# CH32F207_V307V-R3-2v0.net
KiCad netlist of a schematic drawn in Altium Designer
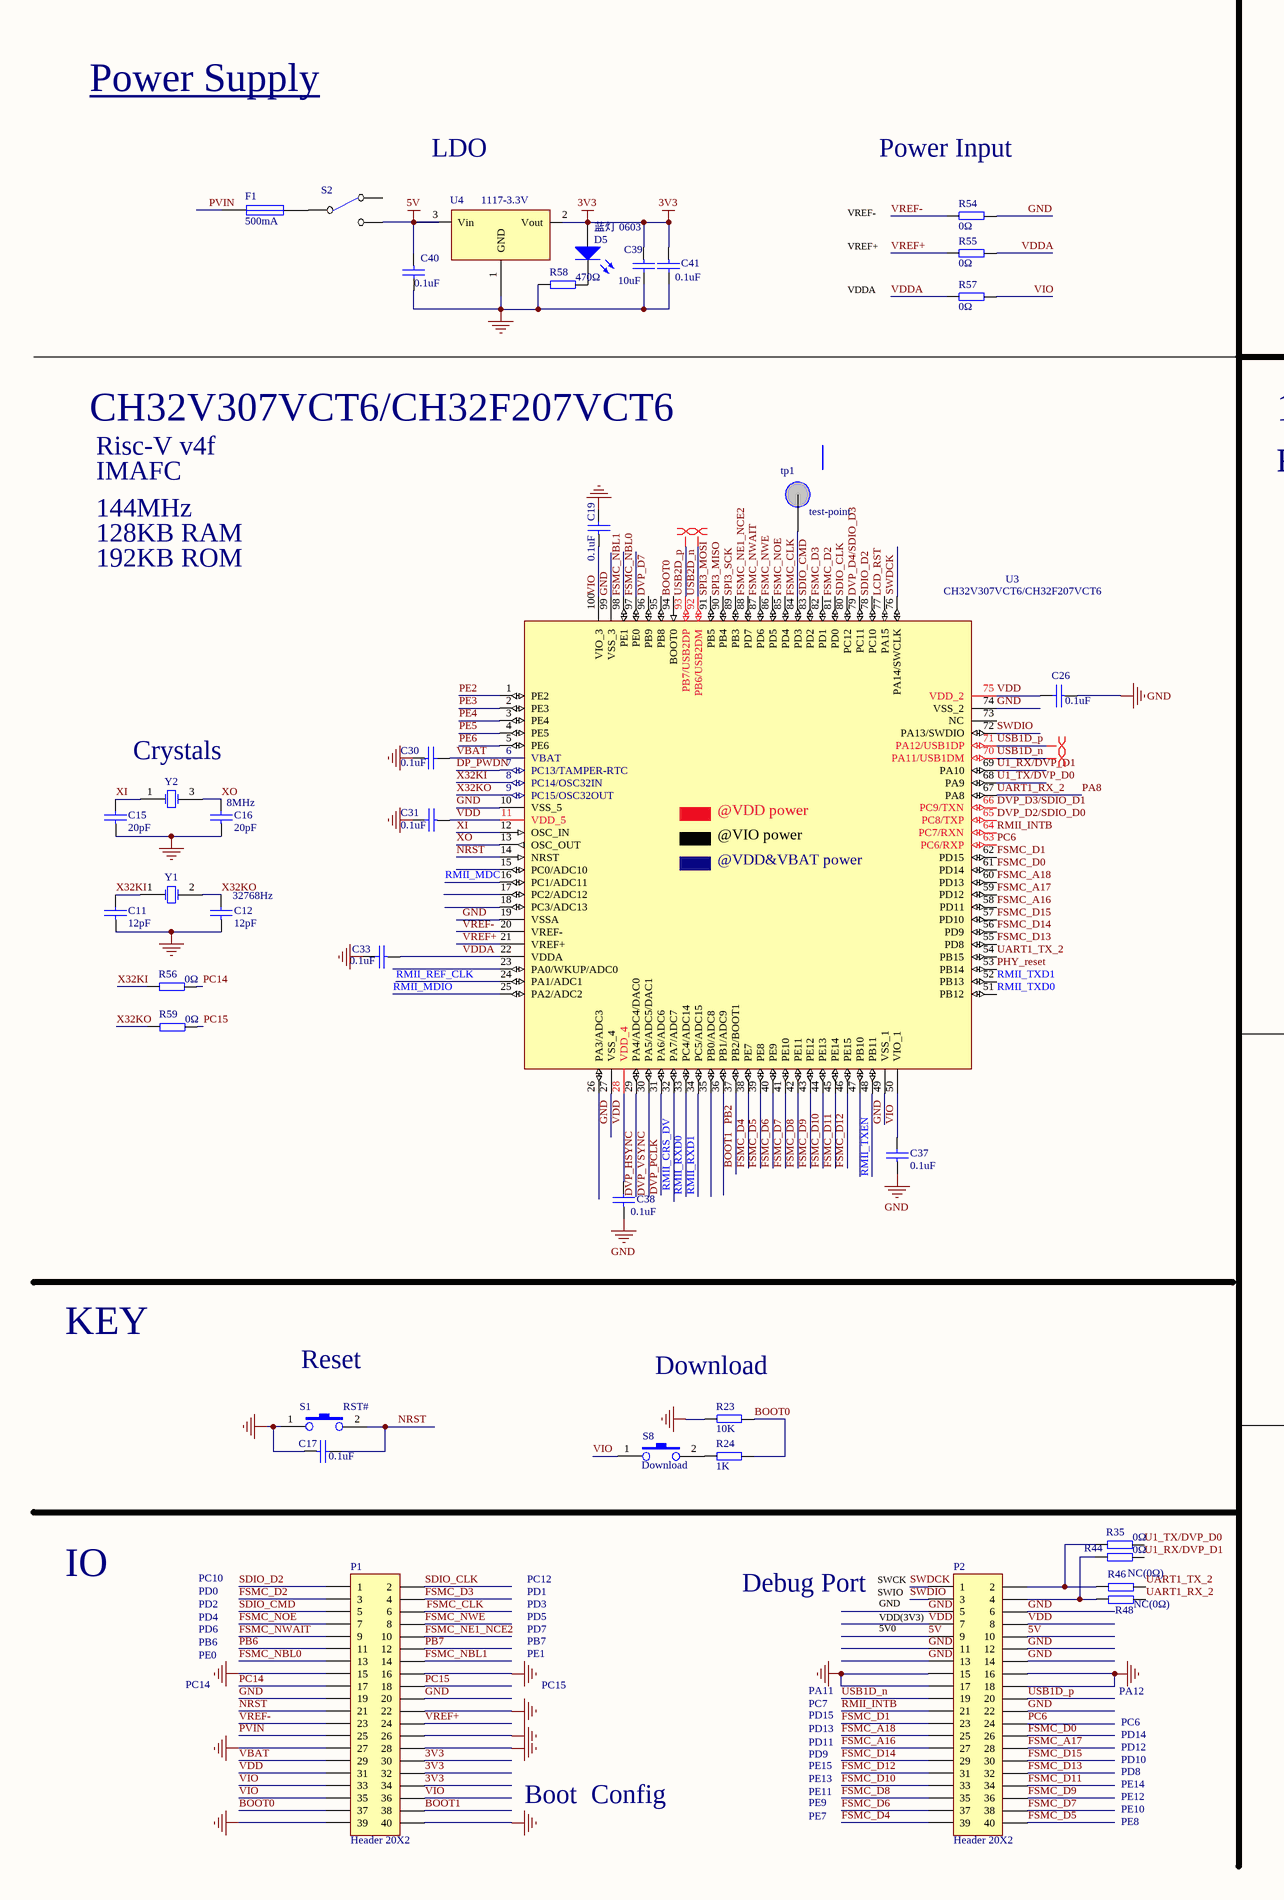
[diagram p0: CH32F207&V307V-R3-2v0.SchDoc, left]
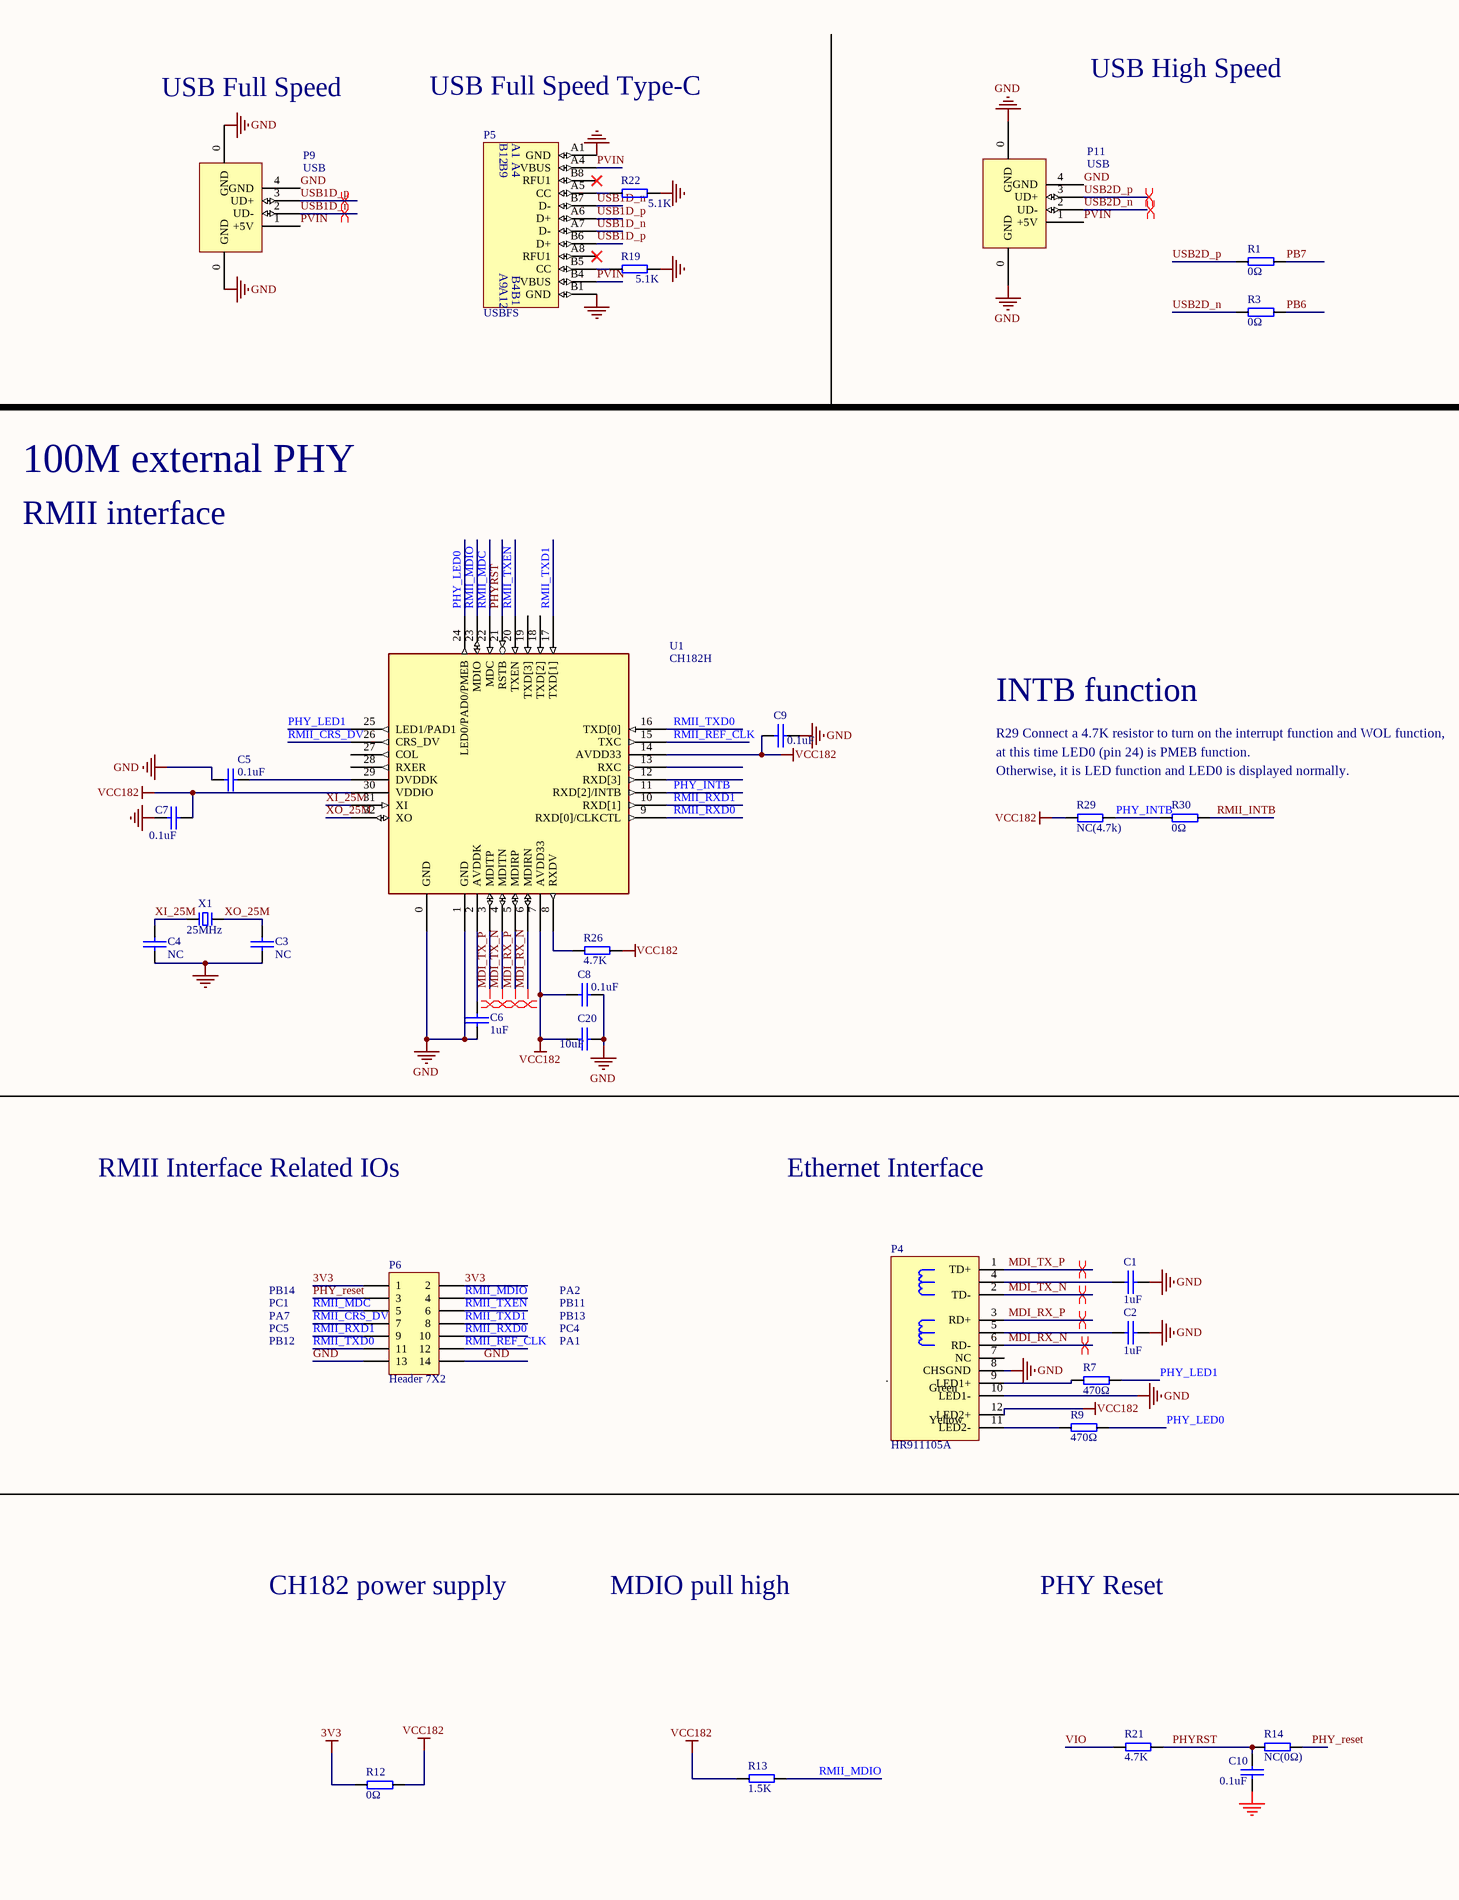
[diagram p1: CH32F207&V307V-R3-2v0.SchDoc, right]

(export (version "E")
  (design (tool "Eeschema 10.0.6"))
  (components
    (comp (ref "C1")
      (value "1uF")
      (footprint "0603_C")
      (description "Capacitor")
      (libsource (lib "wch_sch_others") (part "CAP"))
    )
    (comp (ref "C2")
      (value "1uF")
      (footprint "0603_C")
      (description "Capacitor")
      (libsource (lib "wch_sch_others") (part "CAP"))
    )
    (comp (ref "C3")
      (value "NC")
      (footprint "0603_C")
      (description "Capacitor")
      (libsource (lib "wch_sch_others") (part "CAP"))
    )
    (comp (ref "C4")
      (value "NC")
      (footprint "0603_C")
      (description "Capacitor")
      (libsource (lib "wch_sch_others") (part "CAP"))
    )
    (comp (ref "C5")
      (value "0.1uF")
      (footprint "0603_C")
      (description "Capacitor")
      (libsource (lib "wch_sch_others") (part "CAP"))
    )
    (comp (ref "C6")
      (value "1uF")
      (footprint "0603_C")
      (description "Capacitor")
      (libsource (lib "wch_sch_others") (part "CAP"))
    )
    (comp (ref "C7")
      (value "0.1uF")
      (footprint "0603_C")
      (description "Capacitor")
      (libsource (lib "wch_sch_others") (part "CAP"))
    )
    (comp (ref "C8")
      (value "0.1uF")
      (footprint "0603_C")
      (description "Capacitor")
      (libsource (lib "wch_sch_others") (part "CAP"))
    )
    (comp (ref "C9")
      (value "0.1uF")
      (footprint "0603_C")
      (description "Capacitor")
      (libsource (lib "wch_sch_others") (part "CAP"))
    )
    (comp (ref "C10")
      (value "0.1uF")
      (footprint "0603_C")
      (description "Capacitor")
      (libsource (lib "*") (part "CAP"))
    )
    (comp (ref "C11")
      (value "12pF")
      (footprint "0603_C")
      (description "Capacitor")
      (libsource (lib "*") (part "CAP"))
    )
    (comp (ref "C12")
      (value "12pF")
      (footprint "0603_C")
      (description "Capacitor")
      (libsource (lib "*") (part "CAP"))
    )
    (comp (ref "C15")
      (value "20pF")
      (footprint "0603_C")
      (description "Capacitor")
      (libsource (lib "*") (part "CAP"))
    )
    (comp (ref "C16")
      (value "20pF")
      (footprint "0603_C")
      (description "Capacitor")
      (libsource (lib "*") (part "CAP"))
    )
    (comp (ref "C17")
      (value "0.1uF")
      (footprint "0603_C")
      (description "Capacitor")
      (libsource (lib "") (part "CAP_1"))
    )
    (comp (ref "C19")
      (value "0.1uF")
      (footprint "0603_C")
      (description "Capacitor")
      (libsource (lib "*") (part "CAP"))
    )
    (comp (ref "C20")
      (value "10uF")
      (footprint "0603_C")
      (description "Capacitor")
      (libsource (lib "wch_sch_others") (part "CAP"))
    )
    (comp (ref "C26")
      (value "0.1uF")
      (footprint "0603_C")
      (description "Capacitor")
      (libsource (lib "*") (part "CAP"))
    )
    (comp (ref "C30")
      (value "0.1uF")
      (footprint "0603_C")
      (description "Capacitor")
      (libsource (lib "*") (part "CAP"))
    )
    (comp (ref "C31")
      (value "0.1uF")
      (footprint "0603_C")
      (description "Capacitor")
      (libsource (lib "*") (part "CAP"))
    )
    (comp (ref "C33")
      (value "0.1uF")
      (footprint "0603_C")
      (description "Capacitor")
      (libsource (lib "*") (part "CAP"))
    )
    (comp (ref "C37")
      (value "0.1uF")
      (footprint "0603_C")
      (description "Capacitor")
      (libsource (lib "*") (part "CAP"))
    )
    (comp (ref "C38")
      (value "0.1uF")
      (footprint "0603_C")
      (description "Capacitor")
      (libsource (lib "*") (part "CAP"))
    )
    (comp (ref "C39")
      (value "10uF")
      (footprint "0603_C")
      (description "Capacitor")
      (libsource (lib "*") (part "CAP"))
    )
    (comp (ref "C40")
      (value "0.1uF")
      (footprint "0603_C")
      (description "Capacitor")
      (libsource (lib "*") (part "CAP"))
    )
    (comp (ref "C41")
      (value "0.1uF")
      (footprint "0603_C")
      (description "Capacitor")
      (libsource (lib "*") (part "CAP"))
    )
    (comp (ref "D5")
      (value "蓝灯 0603")
      (footprint "0603_LED_S1")
      (description "发光二极管")
      (libsource (lib "Miscellaneous Devices LC") (part "0603 蓝灯"))
    )
    (comp (ref "F1")
      (value "500mA")
      (footprint "0805")
      (description "Fuse")
      (fields (field (name "PUBLISHER") "Altium Limited"))
      (libsource (lib "Miscellaneous Devices") (part "Fuse 1"))
    )
    (comp (ref "P1")
      (value "Header 20X2")
      (footprint "HDR2X20")
      (description "Header, 20-Pin, Dual row")
      (fields (field (name "PUBLISHER") "Altium Limited"))
      (libsource (lib "Miscellaneous Connectors") (part "Header 20X2"))
    )
    (comp (ref "P2")
      (value "Header 20X2")
      (footprint "HDR2X20")
      (description "Header, 20-Pin, Dual row")
      (fields (field (name "PUBLISHER") "Altium Limited"))
      (libsource (lib "Miscellaneous Connectors") (part "Header 20X2"))
    )
    (comp (ref "P4")
      (value "HR911105A")
      (footprint "HR911105A")
      (libsource (lib "wch_sch_others") (part "HR911105A_1"))
    )
    (comp (ref "P5")
      (value "USBFS")
      (footprint "TYPE-C-Receptacle-2.0")
      (libsource (lib "*") (part "TYPE-C1"))
    )
    (comp (ref "P6")
      (value "Header 7X2")
      (footprint "IDC14-2.54mm")
      (description "Header, 7-Pin, Dual row")
      (fields (field (name "PUBLISHER") "Altium Limited"))
      (libsource (lib "Miscellaneous Connectors") (part "Header 7X2"))
    )
    (comp (ref "P9")
      (value "USB")
      (footprint "USBAF")
      (description "USB Port")
      (libsource (lib "CHXXX") (part "USB"))
    )
    (comp (ref "P11")
      (value "USB")
      (footprint "USBAF")
      (description "USB Port")
      (libsource (lib "CHXXX") (part "USB"))
    )
    (comp (ref "R1") (value "0Ω") (footprint "0603") (libsource (lib "wch_sch_others") (part "RES")))
    (comp (ref "R3") (value "0Ω") (footprint "0603") (libsource (lib "wch_sch_others") (part "RES")))
    (comp (ref "R7") (value "470Ω") (footprint "0603") (libsource (lib "wch_sch_others") (part "RES")))
    (comp (ref "R9") (value "470Ω") (footprint "0603") (libsource (lib "wch_sch_others") (part "RES")))
    (comp (ref "R12") (value "0Ω") (footprint "0603") (libsource (lib "wch_sch_others") (part "RES")))
    (comp (ref "R13") (value "1.5K") (footprint "0603") (libsource (lib "wch_sch_others") (part "RES")))
    (comp (ref "R14") (value "NC(0Ω)") (footprint "0603") (libsource (lib "wch_sch_others") (part "RES")))
    (comp (ref "R19") (value "5.1K") (footprint "0603") (libsource (lib "wch_sch_others") (part "RES")))
    (comp (ref "R21") (value "4.7K") (footprint "0603") (libsource (lib "wch_sch_others") (part "RES")))
    (comp (ref "R22") (value "5.1K") (footprint "0603") (libsource (lib "wch_sch_others") (part "RES")))
    (comp (ref "R23") (value "10K") (footprint "0603") (libsource (lib "wch_sch_others") (part "RES")))
    (comp (ref "R24") (value "1K") (footprint "0603") (libsource (lib "wch_sch_others") (part "RES")))
    (comp (ref "R26") (value "4.7K") (footprint "0603") (libsource (lib "wch_sch_others") (part "RES")))
    (comp (ref "R29") (value "NC(4.7k)") (footprint "0603") (libsource (lib "wch_sch_others") (part "RES")))
    (comp (ref "R30") (value "0Ω") (footprint "0603") (libsource (lib "wch_sch_others") (part "RES")))
    (comp (ref "R35") (value "0Ω") (footprint "0603") (libsource (lib "wch_sch_others") (part "RES")))
    (comp (ref "R44") (value "0Ω") (footprint "0603") (libsource (lib "wch_sch_others") (part "RES")))
    (comp (ref "R46") (value "NC(0Ω)") (footprint "0603") (libsource (lib "wch_sch_others") (part "RES")))
    (comp (ref "R48") (value "NC(0Ω)") (footprint "0603") (libsource (lib "wch_sch_others") (part "RES")))
    (comp (ref "R54") (value "0Ω") (footprint "0603") (libsource (lib "wch_sch_others") (part "RES")))
    (comp (ref "R55") (value "0Ω") (footprint "0603") (libsource (lib "wch_sch_others") (part "RES")))
    (comp (ref "R56") (value "0Ω") (footprint "0603") (libsource (lib "wch_sch_others") (part "RES")))
    (comp (ref "R57") (value "0Ω") (footprint "0603") (libsource (lib "wch_sch_others") (part "RES")))
    (comp (ref "R58") (value "470Ω") (footprint "0603") (libsource (lib "wch_sch_others") (part "RES")))
    (comp (ref "R59") (value "0Ω") (footprint "0603") (libsource (lib "wch_sch_others") (part "RES")))
    (comp (ref "S1")
      (value "RST#")
      (footprint "SMD_6.1x3.65x2.5mm-KEY")
      (libsource (lib "wch_sch_others") (part "KEY1"))
    )
    (comp (ref "S2")
      (value "SW SPDT")
      (footprint "Horizontal Slide Switch_8.7x4.4mm-2D")
      (libsource (lib "*") (part "SW SPDT"))
    )
    (comp (ref "S8")
      (value "Download")
      (footprint "SMD_6.1x3.65x2.5mm-KEY")
      (libsource (lib "wch_sch_others") (part "KEY1"))
    )
    (comp (ref "tp1")
      (value "test-point")
      (footprint "POINT")
      (description "测试点")
      (libsource (lib "五向开关") (part "test-point"))
    )
    (comp (ref "U1")
      (value "CH182H")
      (footprint "QFN32_5X5")
      (description "MII/RMII 10/100M Ethernet PHY (Transceiver) with auto MDIX")
      (libsource (lib "CHXXX") (part "CH182H"))
    )
    (comp (ref "U3")
      (value "CH32V307VCT6/CH32F207VCT6")
      (footprint "LQFP100")
      (description "RISC-V FPU HD-MCU, 144MHz, USB_480M, USB OTG, 1000M Ethernet MAC, 2*CAN, FSMC+DVP")
      (libsource (lib "CHXXX") (part "CH32V307V"))
    )
    (comp (ref "U4")
      (value "1117-3.3V")
      (footprint "SOT-223")
      (libsource (lib "wch_sch_others") (part "1117-3.3V"))
    )
    (comp (ref "X1")
      (value "25MHz")
      (footprint "SMD-3225_4P")
      (description "2脚无源脚晶振")
      (libsource (lib "10.1 - 保险丝-晶振") (part "XTAL-2P"))
    )
    (comp (ref "Y1")
      (value "32768Hz")
      (footprint "FC-135")
      (description "Crystal Oscillator")
      (fields (field (name "PUBLISHER") "Altium Limited"))
      (libsource (lib "*") (part "XTAL"))
    )
    (comp (ref "Y2")
      (value "8MHz")
      (footprint "SMD-3225_4P")
      (description "Crystal Oscillator")
      (fields (field (name "PUBLISHER") "Altium Limited"))
      (libsource (lib "") (part "XTAL_1"))
    )
  )
  (nets
    (net (code "2") (name "/BOOT0") (class "Default")
      (node (ref "P1") (pin "37") (pinfunction "37_37") (pintype "passive"))
      (node (ref "R23") (pin "1") (pintype "passive"))
      (node (ref "R24") (pin "1") (pintype "passive"))
      (node (ref "U3") (pin "94") (pinfunction "BOOT0_94") (pintype "input"))
    )
    (net (code "3") (name "/BOOT1") (class "Default")
      (node (ref "P1") (pin "38") (pinfunction "38_38") (pintype "passive"))
      (node (ref "U3") (pin "37") (pinfunction "PB2/BOOT1_37") (pintype "bidirectional"))
    )
    (net (code "4") (name "/DP_PWDN") (class "Default")
      (node (ref "U3") (pin "7") (pinfunction "PC13/TAMPER-RTC_7") (pintype "bidirectional"))
    )
    (net (code "5") (name "/DVP_D2{slash}SDIO_D0") (class "Default")
      (node (ref "U3") (pin "65") (pinfunction "PC8/TXP_65") (pintype "bidirectional"))
    )
    (net (code "6") (name "/DVP_D3{slash}SDIO_D1") (class "Default")
      (node (ref "U3") (pin "66") (pinfunction "PC9/TXN_66") (pintype "bidirectional"))
    )
    (net (code "7") (name "/DVP_D4{slash}SDIO_D3") (class "Default")
      (node (ref "U3") (pin "79") (pinfunction "PC11_79") (pintype "bidirectional"))
    )
    (net (code "8") (name "/DVP_D7") (class "Default")
      (node (ref "U3") (pin "96") (pinfunction "PB9_96") (pintype "bidirectional"))
    )
    (net (code "9") (name "/DVP_HSYNC") (class "Default")
      (node (ref "U3") (pin "29") (pinfunction "PA4/ADC4/DAC0_29") (pintype "bidirectional"))
    )
    (net (code "10") (name "/DVP_PCLK") (class "Default")
      (node (ref "U3") (pin "31") (pinfunction "PA6/ADC6_31") (pintype "bidirectional"))
    )
    (net (code "11") (name "/DVP_VSYNC") (class "Default")
      (node (ref "U3") (pin "30") (pinfunction "PA5/ADC5/DAC1_30") (pintype "bidirectional"))
    )
    (net (code "12") (name "/FSMC_A16") (class "Default")
      (node (ref "P2") (pin "27") (pinfunction "27_27") (pintype "passive"))
      (node (ref "U3") (pin "58") (pinfunction "PD11_58") (pintype "bidirectional"))
    )
    (net (code "13") (name "/FSMC_A17") (class "Default")
      (node (ref "P2") (pin "28") (pinfunction "28_28") (pintype "passive"))
      (node (ref "U3") (pin "59") (pinfunction "PD12_59") (pintype "bidirectional"))
    )
    (net (code "14") (name "/FSMC_A18") (class "Default")
      (node (ref "P2") (pin "25") (pinfunction "25_25") (pintype "passive"))
      (node (ref "U3") (pin "60") (pinfunction "PD13_60") (pintype "bidirectional"))
    )
    (net (code "15") (name "/FSMC_CLK") (class "Default")
      (node (ref "P1") (pin "6") (pinfunction "6_6") (pintype "passive"))
      (node (ref "U3") (pin "84") (pinfunction "PD3_84") (pintype "bidirectional"))
      (node (ref "tp1") (pin "1") (pinfunction "point_1") (pintype "passive"))
    )
    (net (code "16") (name "/FSMC_D0") (class "Default")
      (node (ref "P2") (pin "26") (pinfunction "26_26") (pintype "passive"))
      (node (ref "U3") (pin "61") (pinfunction "PD14_61") (pintype "bidirectional"))
    )
    (net (code "17") (name "/FSMC_D1") (class "Default")
      (node (ref "P2") (pin "23") (pinfunction "23_23") (pintype "passive"))
      (node (ref "U3") (pin "62") (pinfunction "PD15_62") (pintype "bidirectional"))
    )
    (net (code "18") (name "/FSMC_D2") (class "Default")
      (node (ref "P1") (pin "3") (pinfunction "3_3") (pintype "passive"))
      (node (ref "U3") (pin "81") (pinfunction "PD0_81") (pintype "bidirectional"))
    )
    (net (code "19") (name "/FSMC_D3") (class "Default")
      (node (ref "P1") (pin "4") (pinfunction "4_4") (pintype "passive"))
      (node (ref "U3") (pin "82") (pinfunction "PD1_82") (pintype "bidirectional"))
    )
    (net (code "20") (name "/FSMC_D4") (class "Default")
      (node (ref "P2") (pin "39") (pinfunction "39_39") (pintype "passive"))
      (node (ref "U3") (pin "38") (pinfunction "PE7_38") (pintype "bidirectional"))
    )
    (net (code "21") (name "/FSMC_D5") (class "Default")
      (node (ref "P2") (pin "40") (pinfunction "40_40") (pintype "passive"))
      (node (ref "U3") (pin "39") (pinfunction "PE8_39") (pintype "bidirectional"))
    )
    (net (code "22") (name "/FSMC_D6") (class "Default")
      (node (ref "P2") (pin "37") (pinfunction "37_37") (pintype "passive"))
      (node (ref "U3") (pin "40") (pinfunction "PE9_40") (pintype "bidirectional"))
    )
    (net (code "23") (name "/FSMC_D7") (class "Default")
      (node (ref "P2") (pin "38") (pinfunction "38_38") (pintype "passive"))
      (node (ref "U3") (pin "41") (pinfunction "PE10_41") (pintype "bidirectional"))
    )
    (net (code "24") (name "/FSMC_D8") (class "Default")
      (node (ref "P2") (pin "35") (pinfunction "35_35") (pintype "passive"))
      (node (ref "U3") (pin "42") (pinfunction "PE11_42") (pintype "bidirectional"))
    )
    (net (code "25") (name "/FSMC_D9") (class "Default")
      (node (ref "P2") (pin "36") (pinfunction "36_36") (pintype "passive"))
      (node (ref "U3") (pin "43") (pinfunction "PE12_43") (pintype "bidirectional"))
    )
    (net (code "26") (name "/FSMC_D10") (class "Default")
      (node (ref "P2") (pin "33") (pinfunction "33_33") (pintype "passive"))
      (node (ref "U3") (pin "44") (pinfunction "PE13_44") (pintype "bidirectional"))
    )
    (net (code "27") (name "/FSMC_D11") (class "Default")
      (node (ref "P2") (pin "34") (pinfunction "34_34") (pintype "passive"))
      (node (ref "U3") (pin "45") (pinfunction "PE14_45") (pintype "bidirectional"))
    )
    (net (code "28") (name "/FSMC_D12") (class "Default")
      (node (ref "P2") (pin "31") (pinfunction "31_31") (pintype "passive"))
      (node (ref "U3") (pin "46") (pinfunction "PE15_46") (pintype "bidirectional"))
    )
    (net (code "29") (name "/FSMC_D13") (class "Default")
      (node (ref "P2") (pin "32") (pinfunction "32_32") (pintype "passive"))
      (node (ref "U3") (pin "55") (pinfunction "PD8_55") (pintype "bidirectional"))
    )
    (net (code "30") (name "/FSMC_D14") (class "Default")
      (node (ref "P2") (pin "29") (pinfunction "29_29") (pintype "passive"))
      (node (ref "U3") (pin "56") (pinfunction "PD9_56") (pintype "bidirectional"))
    )
    (net (code "31") (name "/FSMC_D15") (class "Default")
      (node (ref "P2") (pin "30") (pinfunction "30_30") (pintype "passive"))
      (node (ref "U3") (pin "57") (pinfunction "PD10_57") (pintype "bidirectional"))
    )
    (net (code "32") (name "/FSMC_NBL0") (class "Default")
      (node (ref "P1") (pin "13") (pinfunction "13_13") (pintype "passive"))
      (node (ref "U3") (pin "97") (pinfunction "PE0_97") (pintype "bidirectional"))
    )
    (net (code "33") (name "/FSMC_NBL1") (class "Default")
      (node (ref "P1") (pin "14") (pinfunction "14_14") (pintype "passive"))
      (node (ref "U3") (pin "98") (pinfunction "PE1_98") (pintype "bidirectional"))
    )
    (net (code "34") (name "/FSMC_NE1_NCE2") (class "Default")
      (node (ref "P1") (pin "10") (pinfunction "10_10") (pintype "passive"))
      (node (ref "U3") (pin "88") (pinfunction "PD7_88") (pintype "bidirectional"))
    )
    (net (code "35") (name "/FSMC_NOE") (class "Default")
      (node (ref "P1") (pin "7") (pinfunction "7_7") (pintype "passive"))
      (node (ref "U3") (pin "85") (pinfunction "PD4_85") (pintype "bidirectional"))
    )
    (net (code "36") (name "/FSMC_NWAIT") (class "Default")
      (node (ref "P1") (pin "9") (pinfunction "9_9") (pintype "passive"))
      (node (ref "U3") (pin "87") (pinfunction "PD6_87") (pintype "bidirectional"))
    )
    (net (code "37") (name "/FSMC_NWE") (class "Default")
      (node (ref "P1") (pin "8") (pinfunction "8_8") (pintype "passive"))
      (node (ref "U3") (pin "86") (pinfunction "PD5_86") (pintype "bidirectional"))
    )
    (net (code "38") (name "/LCD_RST") (class "Default")
      (node (ref "U3") (pin "77") (pinfunction "PA15_77") (pintype "bidirectional"))
    )
    (net (code "39") (name "/MDI_RX_N") (class "Default")
      (node (ref "P4") (pin "6") (pinfunction "RD-_6") (pintype "passive"))
      (node (ref "U1") (pin "6") (pinfunction "MDIRN_6") (pintype "bidirectional"))
    )
    (net (code "40") (name "/MDI_RX_P") (class "Default")
      (node (ref "P4") (pin "3") (pinfunction "RD+_3") (pintype "passive"))
      (node (ref "U1") (pin "5") (pinfunction "MDIRP_5") (pintype "bidirectional"))
    )
    (net (code "41") (name "/MDI_TX_N") (class "Default")
      (node (ref "P4") (pin "2") (pinfunction "TD-_2") (pintype "passive"))
      (node (ref "U1") (pin "4") (pinfunction "MDITN_4") (pintype "bidirectional"))
    )
    (net (code "42") (name "/MDI_TX_P") (class "Default")
      (node (ref "P4") (pin "1") (pinfunction "TD+_1") (pintype "passive"))
      (node (ref "U1") (pin "3") (pinfunction "MDITP_3") (pintype "bidirectional"))
    )
    (net (code "43") (name "/NRST") (class "Default")
      (node (ref "C17") (pin "2") (pinfunction "2_2") (pintype "passive"))
      (node (ref "P1") (pin "21") (pinfunction "21_21") (pintype "passive"))
      (node (ref "S1") (pin "2") (pinfunction "2_2") (pintype "passive"))
      (node (ref "U3") (pin "14") (pinfunction "NRST_14") (pintype "input"))
    )
    (net (code "44") (name "/PA8") (class "Default")
      (node (ref "R48") (pin "2") (pintype "passive"))
      (node (ref "U3") (pin "67") (pinfunction "PA8_67") (pintype "bidirectional"))
    )
    (net (code "45") (name "/PB6") (class "Default")
      (node (ref "P1") (pin "11") (pinfunction "11_11") (pintype "passive"))
      (node (ref "R3") (pin "2") (pintype "passive"))
    )
    (net (code "46") (name "/PB7") (class "Default")
      (node (ref "P1") (pin "12") (pinfunction "12_12") (pintype "passive"))
      (node (ref "R1") (pin "2") (pintype "passive"))
    )
    (net (code "47") (name "/PC6") (class "Default")
      (node (ref "P2") (pin "24") (pinfunction "24_24") (pintype "passive"))
      (node (ref "U3") (pin "63") (pinfunction "PC6/RXP_63") (pintype "bidirectional"))
    )
    (net (code "48") (name "/PC14") (class "Default")
      (node (ref "P1") (pin "17") (pinfunction "17_17") (pintype "passive"))
      (node (ref "R56") (pin "2") (pintype "passive"))
    )
    (net (code "49") (name "/PC15") (class "Default")
      (node (ref "P1") (pin "18") (pinfunction "18_18") (pintype "passive"))
      (node (ref "R59") (pin "2") (pintype "passive"))
    )
    (net (code "50") (name "/PE2") (class "Default")
      (node (ref "U3") (pin "1") (pinfunction "PE2_1") (pintype "bidirectional"))
    )
    (net (code "51") (name "/PE3") (class "Default")
      (node (ref "U3") (pin "2") (pinfunction "PE3_2") (pintype "bidirectional"))
    )
    (net (code "52") (name "/PE4") (class "Default")
      (node (ref "U3") (pin "3") (pinfunction "PE4_3") (pintype "bidirectional"))
    )
    (net (code "53") (name "/PE5") (class "Default")
      (node (ref "U3") (pin "4") (pinfunction "PE5_4") (pintype "bidirectional"))
    )
    (net (code "54") (name "/PE6") (class "Default")
      (node (ref "U3") (pin "5") (pinfunction "PE6_5") (pintype "bidirectional"))
    )
    (net (code "55") (name "/PHYRST") (class "Default")
      (node (ref "C10") (pin "2") (pinfunction "2_2") (pintype "passive"))
      (node (ref "R14") (pin "1") (pintype "passive"))
      (node (ref "R21") (pin "1") (pintype "passive"))
      (node (ref "U1") (pin "21") (pinfunction "RSTB_21") (pintype "input"))
    )
    (net (code "56") (name "/PHY_INTB") (class "Default")
      (node (ref "R29") (pin "1") (pintype "passive"))
      (node (ref "R30") (pin "1") (pintype "passive"))
      (node (ref "U1") (pin "11") (pinfunction "RXD[2]/INTB_11") (pintype "output"))
    )
    (net (code "57") (name "/PHY_LED0") (class "Default")
      (node (ref "R9") (pin "2") (pintype "passive"))
      (node (ref "U1") (pin "24") (pinfunction "LED0/PAD0/PMEB_24") (pintype "output"))
    )
    (net (code "58") (name "/PHY_LED1") (class "Default")
      (node (ref "R7") (pin "2") (pintype "passive"))
      (node (ref "U1") (pin "25") (pinfunction "LED1/PAD1_25") (pintype "output"))
    )
    (net (code "59") (name "/PHY_reset") (class "Default")
      (node (ref "P6") (pin "3") (pinfunction "3_3") (pintype "passive"))
      (node (ref "R14") (pin "2") (pintype "passive"))
      (node (ref "U3") (pin "53") (pinfunction "PB14_53") (pintype "bidirectional"))
    )
    (net (code "60") (name "/PVIN") (class "Default")
      (node (ref "F1") (pin "1") (pinfunction "1_1") (pintype "passive"))
      (node (ref "P1") (pin "25") (pinfunction "25_25") (pintype "passive"))
      (node (ref "P11") (pin "1") (pinfunction "+5V_1") (pintype "power_in"))
      (node (ref "P5") (pin "A4") (pinfunction "VBUS_A4") (pintype "bidirectional"))
      (node (ref "P5") (pin "B4") (pinfunction "VBUS_B4") (pintype "bidirectional"))
      (node (ref "P9") (pin "1") (pinfunction "+5V_1") (pintype "power_in"))
    )
    (net (code "61") (name "/RMII_CRS_DV") (class "Default")
      (node (ref "P6") (pin "7") (pinfunction "7_7") (pintype "passive"))
      (node (ref "U1") (pin "26") (pinfunction "CRS_DV_26") (pintype "output"))
      (node (ref "U3") (pin "32") (pinfunction "PA7/ADC7_32") (pintype "bidirectional"))
    )
    (net (code "62") (name "/RMII_INTB") (class "Default")
      (node (ref "P2") (pin "21") (pinfunction "21_21") (pintype "passive"))
      (node (ref "R30") (pin "2") (pintype "passive"))
      (node (ref "U3") (pin "64") (pinfunction "PC7/RXN_64") (pintype "bidirectional"))
    )
    (net (code "63") (name "/RMII_MDC") (class "Default")
      (node (ref "P6") (pin "5") (pinfunction "5_5") (pintype "passive"))
      (node (ref "U1") (pin "22") (pinfunction "MDC_22") (pintype "input"))
      (node (ref "U3") (pin "16") (pinfunction "PC1/ADC11_16") (pintype "bidirectional"))
    )
    (net (code "64") (name "/RMII_MDIO") (class "Default")
      (node (ref "P6") (pin "4") (pinfunction "4_4") (pintype "passive"))
      (node (ref "R13") (pin "2") (pintype "passive"))
      (node (ref "U1") (pin "23") (pinfunction "MDIO_23") (pintype "bidirectional"))
      (node (ref "U3") (pin "25") (pinfunction "PA2/ADC2_25") (pintype "bidirectional"))
    )
    (net (code "65") (name "/RMII_REF_CLK") (class "Default")
      (node (ref "P6") (pin "12") (pinfunction "12_12") (pintype "passive"))
      (node (ref "U1") (pin "15") (pinfunction "TXC_15") (pintype "output"))
      (node (ref "U3") (pin "24") (pinfunction "PA1/ADC1_24") (pintype "bidirectional"))
    )
    (net (code "66") (name "/RMII_RXD0") (class "Default")
      (node (ref "P6") (pin "10") (pinfunction "10_10") (pintype "passive"))
      (node (ref "U1") (pin "9") (pinfunction "RXD[0]/CLKCTL_9") (pintype "output"))
      (node (ref "U3") (pin "33") (pinfunction "PC4/ADC14_33") (pintype "bidirectional"))
    )
    (net (code "67") (name "/RMII_RXD1") (class "Default")
      (node (ref "P6") (pin "9") (pinfunction "9_9") (pintype "passive"))
      (node (ref "U1") (pin "10") (pinfunction "RXD[1]_10") (pintype "output"))
      (node (ref "U3") (pin "34") (pinfunction "PC5/ADC15_34") (pintype "bidirectional"))
    )
    (net (code "68") (name "/RMII_TXD0") (class "Default")
      (node (ref "P6") (pin "11") (pinfunction "11_11") (pintype "passive"))
      (node (ref "U1") (pin "16") (pinfunction "TXD[0]_16") (pintype "input"))
      (node (ref "U3") (pin "51") (pinfunction "PB12_51") (pintype "bidirectional"))
    )
    (net (code "69") (name "/RMII_TXD1") (class "Default")
      (node (ref "P6") (pin "8") (pinfunction "8_8") (pintype "passive"))
      (node (ref "U1") (pin "17") (pinfunction "TXD[1]_17") (pintype "input"))
      (node (ref "U3") (pin "52") (pinfunction "PB13_52") (pintype "bidirectional"))
    )
    (net (code "70") (name "/RMII_TXEN") (class "Default")
      (node (ref "P6") (pin "6") (pinfunction "6_6") (pintype "passive"))
      (node (ref "U1") (pin "20") (pinfunction "TXEN_20") (pintype "input"))
      (node (ref "U3") (pin "48") (pinfunction "PB11_48") (pintype "bidirectional"))
    )
    (net (code "71") (name "/SDIO_CLK") (class "Default")
      (node (ref "P1") (pin "2") (pinfunction "2_2") (pintype "passive"))
      (node (ref "U3") (pin "80") (pinfunction "PC12_80") (pintype "bidirectional"))
    )
    (net (code "72") (name "/SDIO_CMD") (class "Default")
      (node (ref "P1") (pin "5") (pinfunction "5_5") (pintype "passive"))
      (node (ref "U3") (pin "83") (pinfunction "PD2_83") (pintype "bidirectional"))
    )
    (net (code "73") (name "/SDIO_D2") (class "Default")
      (node (ref "P1") (pin "1") (pinfunction "1_1") (pintype "passive"))
      (node (ref "U3") (pin "78") (pinfunction "PC10_78") (pintype "bidirectional"))
    )
    (net (code "74") (name "/SPI3_MISO") (class "Default")
      (node (ref "U3") (pin "90") (pinfunction "PB4_90") (pintype "bidirectional"))
    )
    (net (code "75") (name "/SPI3_MOSI") (class "Default")
      (node (ref "U3") (pin "91") (pinfunction "PB5_91") (pintype "bidirectional"))
    )
    (net (code "76") (name "/SPI3_SCK") (class "Default")
      (node (ref "U3") (pin "89") (pinfunction "PB3_89") (pintype "bidirectional"))
    )
    (net (code "77") (name "/SWDCK") (class "Default")
      (node (ref "P2") (pin "1") (pinfunction "1_1") (pintype "passive"))
      (node (ref "U3") (pin "76") (pinfunction "PA14/SWCLK_76") (pintype "bidirectional"))
    )
    (net (code "78") (name "/SWDIO") (class "Default")
      (node (ref "P2") (pin "3") (pinfunction "3_3") (pintype "passive"))
      (node (ref "U3") (pin "72") (pinfunction "PA13/SWDIO_72") (pintype "bidirectional"))
    )
    (net (code "79") (name "/U1_RX{slash}DVP_D1") (class "Default")
      (node (ref "R44") (pin "2") (pintype "passive"))
      (node (ref "U3") (pin "69") (pinfunction "PA10_69") (pintype "bidirectional"))
    )
    (net (code "80") (name "/U1_TX{slash}DVP_D0") (class "Default")
      (node (ref "R35") (pin "2") (pintype "passive"))
      (node (ref "U3") (pin "68") (pinfunction "PA9_68") (pintype "bidirectional"))
    )
    (net (code "81") (name "/UART1_TX_2") (class "Default")
      (node (ref "R46") (pin "2") (pintype "passive"))
      (node (ref "U3") (pin "54") (pinfunction "PB15_54") (pintype "bidirectional"))
    )
    (net (code "82") (name "/USB1D_n") (class "Default")
      (node (ref "P2") (pin "19") (pinfunction "19_19") (pintype "passive"))
      (node (ref "P5") (pin "A7") (pinfunction "D-_A7") (pintype "bidirectional"))
      (node (ref "P5") (pin "B7") (pinfunction "D-_B7") (pintype "bidirectional"))
      (node (ref "P9") (pin "2") (pinfunction "UD-_2") (pintype "bidirectional"))
      (node (ref "U3") (pin "70") (pinfunction "PA11/USB1DM_70") (pintype "bidirectional"))
    )
    (net (code "83") (name "/USB1D_p") (class "Default")
      (node (ref "P2") (pin "20") (pinfunction "20_20") (pintype "passive"))
      (node (ref "P5") (pin "A6") (pinfunction "D+_A6") (pintype "bidirectional"))
      (node (ref "P5") (pin "B6") (pinfunction "D+_B6") (pintype "bidirectional"))
      (node (ref "P9") (pin "3") (pinfunction "UD+_3") (pintype "bidirectional"))
      (node (ref "U3") (pin "71") (pinfunction "PA12/USB1DP_71") (pintype "bidirectional"))
    )
    (net (code "84") (name "/USB2D_n") (class "Default")
      (node (ref "P11") (pin "2") (pinfunction "UD-_2") (pintype "bidirectional"))
      (node (ref "R3") (pin "1") (pintype "passive"))
      (node (ref "U3") (pin "92") (pinfunction "PB6/USB2DM_92") (pintype "bidirectional"))
    )
    (net (code "85") (name "/USB2D_p") (class "Default")
      (node (ref "P11") (pin "3") (pinfunction "UD+_3") (pintype "bidirectional"))
      (node (ref "R1") (pin "1") (pintype "passive"))
      (node (ref "U3") (pin "93") (pinfunction "PB7/USB2DP_93") (pintype "bidirectional"))
    )
    (net (code "86") (name "/VBAT") (class "Default")
      (node (ref "C30") (pin "2") (pinfunction "2_2") (pintype "passive"))
      (node (ref "P1") (pin "29") (pinfunction "29_29") (pintype "passive"))
      (node (ref "U3") (pin "6") (pinfunction "VBAT_6") (pintype "power_in"))
    )
    (net (code "87") (name "/VDD") (class "Default")
      (node (ref "C26") (pin "2") (pinfunction "2_2") (pintype "passive"))
      (node (ref "C31") (pin "1") (pinfunction "1_1") (pintype "passive"))
      (node (ref "C38") (pin "2") (pinfunction "2_2") (pintype "passive"))
      (node (ref "P1") (pin "31") (pinfunction "31_31") (pintype "passive"))
      (node (ref "P2") (pin "7") (pinfunction "7_7") (pintype "passive"))
      (node (ref "P2") (pin "8") (pinfunction "8_8") (pintype "passive"))
      (node (ref "U3") (pin "11") (pinfunction "VDD_5_11") (pintype "power_in"))
      (node (ref "U3") (pin "28") (pinfunction "VDD_4_28") (pintype "power_in"))
      (node (ref "U3") (pin "75") (pinfunction "VDD_2_75") (pintype "power_in"))
    )
    (net (code "88") (name "/VDDA") (class "Default")
      (node (ref "C33") (pin "1") (pinfunction "1_1") (pintype "passive"))
      (node (ref "R55") (pin "1") (pintype "passive"))
      (node (ref "R57") (pin "2") (pintype "passive"))
      (node (ref "U3") (pin "22") (pinfunction "VDDA_22") (pintype "power_in"))
    )
    (net (code "89") (name "/VIO") (class "Default")
      (node (ref "C19") (pin "1") (pinfunction "1_1") (pintype "passive"))
      (node (ref "C37") (pin "2") (pinfunction "2_2") (pintype "passive"))
      (node (ref "P1") (pin "33") (pinfunction "33_33") (pintype "passive"))
      (node (ref "P1") (pin "35") (pinfunction "35_35") (pintype "passive"))
      (node (ref "P1") (pin "36") (pinfunction "36_36") (pintype "passive"))
      (node (ref "R21") (pin "2") (pintype "passive"))
      (node (ref "R57") (pin "1") (pintype "passive"))
      (node (ref "S8") (pin "1") (pinfunction "1_1") (pintype "passive"))
      (node (ref "U3") (pin "100") (pinfunction "VIO_3_100") (pintype "power_in"))
      (node (ref "U3") (pin "50") (pinfunction "VIO_1_50") (pintype "power_in"))
    )
    (net (code "90") (name "/VREF+") (class "Default")
      (node (ref "P1") (pin "24") (pinfunction "24_24") (pintype "passive"))
      (node (ref "R55") (pin "2") (pintype "passive"))
      (node (ref "U3") (pin "21") (pinfunction "VREF+_21") (pintype "power_in"))
    )
    (net (code "91") (name "/VREF-") (class "Default")
      (node (ref "P1") (pin "23") (pinfunction "23_23") (pintype "passive"))
      (node (ref "R54") (pin "2") (pintype "passive"))
      (node (ref "U3") (pin "20") (pinfunction "VREF-_20") (pintype "power_in"))
    )
    (net (code "92") (name "/X32KI") (class "Default")
      (node (ref "C11") (pin "2") (pinfunction "2_2") (pintype "passive"))
      (node (ref "R56") (pin "1") (pintype "passive"))
      (node (ref "U3") (pin "8") (pinfunction "PC14/OSC32IN_8") (pintype "bidirectional"))
      (node (ref "Y1") (pin "1") (pinfunction "OSC1_1") (pintype "passive"))
    )
    (net (code "93") (name "/X32KO") (class "Default")
      (node (ref "C12") (pin "2") (pinfunction "2_2") (pintype "passive"))
      (node (ref "R59") (pin "1") (pintype "passive"))
      (node (ref "U3") (pin "9") (pinfunction "PC15/OSC32OUT_9") (pintype "bidirectional"))
      (node (ref "Y1") (pin "2") (pinfunction "OSC2_2") (pintype "passive"))
    )
    (net (code "94") (name "/XI") (class "Default")
      (node (ref "C15") (pin "2") (pinfunction "2_2") (pintype "passive"))
      (node (ref "U3") (pin "12") (pinfunction "OSC_IN_12") (pintype "input"))
      (node (ref "Y2") (pin "1") (pinfunction "OSC1_1") (pintype "passive"))
    )
    (net (code "95") (name "/XI_25M") (class "Default")
      (node (ref "C4") (pin "2") (pinfunction "2_2") (pintype "passive"))
      (node (ref "U1") (pin "31") (pinfunction "XI_31") (pintype "input"))
      (node (ref "X1") (pin "1") (pinfunction "1_1") (pintype "passive"))
    )
    (net (code "96") (name "/XO") (class "Default")
      (node (ref "C16") (pin "2") (pinfunction "2_2") (pintype "passive"))
      (node (ref "U3") (pin "13") (pinfunction "OSC_OUT_13") (pintype "output"))
      (node (ref "Y2") (pin "3") (pinfunction "OSC2_3") (pintype "passive"))
    )
    (net (code "97") (name "/XO_25M") (class "Default")
      (node (ref "C3") (pin "2") (pinfunction "2_2") (pintype "passive"))
      (node (ref "U1") (pin "32") (pinfunction "XO_32") (pintype "bidirectional"))
      (node (ref "X1") (pin "3") (pinfunction "2_3") (pintype "passive"))
    )
    (net (code "98") (name "3V3") (class "Default")
      (node (ref "C39") (pin "1") (pinfunction "1_1") (pintype "passive"))
      (node (ref "C41") (pin "1") (pinfunction "1_1") (pintype "passive"))
      (node (ref "D5") (pin "A") (pinfunction "A_A") (pintype "passive"))
      (node (ref "P1") (pin "30") (pinfunction "30_30") (pintype "passive"))
      (node (ref "P1") (pin "32") (pinfunction "32_32") (pintype "passive"))
      (node (ref "P1") (pin "34") (pinfunction "34_34") (pintype "passive"))
      (node (ref "P6") (pin "1") (pinfunction "1_1") (pintype "passive"))
      (node (ref "P6") (pin "2") (pinfunction "2_2") (pintype "passive"))
      (node (ref "R12") (pin "2") (pintype "passive"))
      (node (ref "U4") (pin "2") (pinfunction "Vout_2") (pintype "passive"))
    )
    (net (code "99") (name "5V") (class "Default")
      (node (ref "C40") (pin "1") (pinfunction "1_1") (pintype "passive"))
      (node (ref "P2") (pin "10") (pinfunction "10_10") (pintype "passive"))
      (node (ref "P2") (pin "9") (pinfunction "9_9") (pintype "passive"))
      (node (ref "S2") (pin "2") (pinfunction "NC_2") (pintype "passive"))
      (node (ref "U4") (pin "3") (pinfunction "Vin_3") (pintype "passive"))
    )
    (net (code "100") (name "GND") (class "Default")
      (node (ref "C1") (pin "1") (pinfunction "1_1") (pintype "passive"))
      (node (ref "C10") (pin "1") (pinfunction "1_1") (pintype "passive"))
      (node (ref "C11") (pin "1") (pinfunction "1_1") (pintype "passive"))
      (node (ref "C12") (pin "1") (pinfunction "1_1") (pintype "passive"))
      (node (ref "C15") (pin "1") (pinfunction "1_1") (pintype "passive"))
      (node (ref "C16") (pin "1") (pinfunction "1_1") (pintype "passive"))
      (node (ref "C17") (pin "1") (pinfunction "1_1") (pintype "passive"))
      (node (ref "C19") (pin "2") (pinfunction "2_2") (pintype "passive"))
      (node (ref "C2") (pin "1") (pinfunction "1_1") (pintype "passive"))
      (node (ref "C20") (pin "1") (pinfunction "1_1") (pintype "passive"))
      (node (ref "C26") (pin "1") (pinfunction "1_1") (pintype "passive"))
      (node (ref "C3") (pin "1") (pinfunction "1_1") (pintype "passive"))
      (node (ref "C30") (pin "1") (pinfunction "1_1") (pintype "passive"))
      (node (ref "C31") (pin "2") (pinfunction "2_2") (pintype "passive"))
      (node (ref "C33") (pin "2") (pinfunction "2_2") (pintype "passive"))
      (node (ref "C37") (pin "1") (pinfunction "1_1") (pintype "passive"))
      (node (ref "C38") (pin "1") (pinfunction "1_1") (pintype "passive"))
      (node (ref "C39") (pin "2") (pinfunction "2_2") (pintype "passive"))
      (node (ref "C4") (pin "1") (pinfunction "1_1") (pintype "passive"))
      (node (ref "C40") (pin "2") (pinfunction "2_2") (pintype "passive"))
      (node (ref "C41") (pin "2") (pinfunction "2_2") (pintype "passive"))
      (node (ref "C5") (pin "1") (pinfunction "1_1") (pintype "passive"))
      (node (ref "C6") (pin "1") (pinfunction "1_1") (pintype "passive"))
      (node (ref "C7") (pin "1") (pinfunction "1_1") (pintype "passive"))
      (node (ref "C8") (pin "1") (pinfunction "1_1") (pintype "passive"))
      (node (ref "C9") (pin "1") (pinfunction "1_1") (pintype "passive"))
      (node (ref "P1") (pin "15") (pinfunction "15_15") (pintype "passive"))
      (node (ref "P1") (pin "16") (pinfunction "16_16") (pintype "passive"))
      (node (ref "P1") (pin "19") (pinfunction "19_19") (pintype "passive"))
      (node (ref "P1") (pin "20") (pinfunction "20_20") (pintype "passive"))
      (node (ref "P1") (pin "22") (pinfunction "22_22") (pintype "passive"))
      (node (ref "P1") (pin "26") (pinfunction "26_26") (pintype "passive"))
      (node (ref "P1") (pin "27") (pinfunction "27_27") (pintype "passive"))
      (node (ref "P1") (pin "28") (pinfunction "28_28") (pintype "passive"))
      (node (ref "P1") (pin "39") (pinfunction "39_39") (pintype "passive"))
      (node (ref "P1") (pin "40") (pinfunction "40_40") (pintype "passive"))
      (node (ref "P11") (pin "0") (pinfunction "GND_0") (pintype "power_in"))
      (node (ref "P11") (pin "4") (pinfunction "GND_4") (pintype "power_in"))
      (node (ref "P2") (pin "11") (pinfunction "11_11") (pintype "passive"))
      (node (ref "P2") (pin "12") (pinfunction "12_12") (pintype "passive"))
      (node (ref "P2") (pin "13") (pinfunction "13_13") (pintype "passive"))
      (node (ref "P2") (pin "14") (pinfunction "14_14") (pintype "passive"))
      (node (ref "P2") (pin "15") (pinfunction "15_15") (pintype "passive"))
      (node (ref "P2") (pin "16") (pinfunction "16_16") (pintype "passive"))
      (node (ref "P2") (pin "17") (pinfunction "17_17") (pintype "passive"))
      (node (ref "P2") (pin "18") (pinfunction "18_18") (pintype "passive"))
      (node (ref "P2") (pin "22") (pinfunction "22_22") (pintype "passive"))
      (node (ref "P2") (pin "5") (pinfunction "5_5") (pintype "passive"))
      (node (ref "P2") (pin "6") (pinfunction "6_6") (pintype "passive"))
      (node (ref "P4") (pin "10") (pinfunction "LED1-_10") (pintype "passive"))
      (node (ref "P4") (pin "8") (pinfunction "CHSGND_8") (pintype "passive"))
      (node (ref "P5") (pin "A1") (pinfunction "GND_A1") (pintype "bidirectional"))
      (node (ref "P5") (pin "B1") (pinfunction "GND_B1") (pintype "bidirectional"))
      (node (ref "P6") (pin "13") (pinfunction "13_13") (pintype "passive"))
      (node (ref "P6") (pin "14") (pinfunction "14_14") (pintype "passive"))
      (node (ref "P9") (pin "0") (pinfunction "GND_0") (pintype "power_in"))
      (node (ref "P9") (pin "4") (pinfunction "GND_4") (pintype "power_in"))
      (node (ref "R19") (pin "2") (pintype "passive"))
      (node (ref "R22") (pin "2") (pintype "passive"))
      (node (ref "R23") (pin "2") (pintype "passive"))
      (node (ref "R54") (pin "1") (pintype "passive"))
      (node (ref "R58") (pin "1") (pintype "passive"))
      (node (ref "S1") (pin "1") (pinfunction "1_1") (pintype "passive"))
      (node (ref "U1") (pin "0") (pinfunction "GND_0") (pintype "power_in"))
      (node (ref "U1") (pin "1") (pinfunction "GND_1") (pintype "power_in"))
      (node (ref "U3") (pin "10") (pinfunction "VSS_5_10") (pintype "power_in"))
      (node (ref "U3") (pin "19") (pinfunction "VSSA_19") (pintype "power_in"))
      (node (ref "U3") (pin "27") (pinfunction "VSS_4_27") (pintype "power_in"))
      (node (ref "U3") (pin "49") (pinfunction "VSS_1_49") (pintype "power_in"))
      (node (ref "U3") (pin "74") (pinfunction "VSS_2_74") (pintype "power_in"))
      (node (ref "U3") (pin "99") (pinfunction "VSS_3_99") (pintype "power_in"))
      (node (ref "U4") (pin "1") (pinfunction "GND_1") (pintype "passive"))
    )
    (net (code "101") (name "Net-(C1-Pad2)") (class "Default")
      (node (ref "C1") (pin "2") (pinfunction "2_2") (pintype "passive"))
      (node (ref "P4") (pin "4") (pintype "passive"))
    )
    (net (code "102") (name "Net-(C2-Pad2)") (class "Default")
      (node (ref "C2") (pin "2") (pinfunction "2_2") (pintype "passive"))
      (node (ref "P4") (pin "5") (pintype "passive"))
    )
    (net (code "103") (name "Net-(D5-PadK)") (class "Default")
      (node (ref "D5") (pin "K") (pinfunction "K_K") (pintype "passive"))
      (node (ref "R58") (pin "2") (pintype "passive"))
    )
    (net (code "104") (name "Net-(P2-Pad2)") (class "Default")
      (node (ref "P2") (pin "2") (pinfunction "2_2") (pintype "passive"))
      (node (ref "R35") (pin "1") (pintype "passive"))
      (node (ref "R46") (pin "1") (pintype "passive"))
    )
    (net (code "105") (name "Net-(P2-Pad4)") (class "Default")
      (node (ref "P2") (pin "4") (pinfunction "4_4") (pintype "passive"))
      (node (ref "R44") (pin "1") (pintype "passive"))
      (node (ref "R48") (pin "1") (pintype "passive"))
    )
    (net (code "106") (name "Net-(P4-LED1+)") (class "Default")
      (node (ref "P4") (pin "9") (pinfunction "LED1+_9") (pintype "passive"))
      (node (ref "R7") (pin "1") (pintype "passive"))
    )
    (net (code "107") (name "Net-(P4-LED2-)") (class "Default")
      (node (ref "P4") (pin "11") (pinfunction "LED2-_11") (pintype "passive"))
      (node (ref "R9") (pin "1") (pintype "passive"))
    )
    (net (code "108") (name "Net-(P5-CC-PadA5)") (class "Default")
      (node (ref "P5") (pin "A5") (pinfunction "CC_A5") (pintype "bidirectional"))
      (node (ref "R22") (pin "1") (pintype "passive"))
    )
    (net (code "109") (name "Net-(P5-CC-PadB5)") (class "Default")
      (node (ref "P5") (pin "B5") (pinfunction "CC_B5") (pintype "bidirectional"))
      (node (ref "R19") (pin "1") (pintype "passive"))
    )
    (net (code "110") (name "Net-(R24-Pad2)") (class "Default")
      (node (ref "R24") (pin "2") (pintype "passive"))
      (node (ref "S8") (pin "2") (pinfunction "2_2") (pintype "passive"))
    )
    (net (code "111") (name "Net-(S2-COMMON)") (class "Default")
      (node (ref "F1") (pin "2") (pinfunction "2_2") (pintype "passive"))
      (node (ref "S2") (pin "1") (pinfunction "COMMON_1") (pintype "passive"))
    )
    (net (code "112") (name "Net-(U1-AVDDK)") (class "Default")
      (node (ref "C6") (pin "2") (pinfunction "2_2") (pintype "passive"))
      (node (ref "U1") (pin "2") (pinfunction "AVDDK_2") (pintype "power_in"))
    )
    (net (code "113") (name "Net-(U1-DVDDK)") (class "Default")
      (node (ref "C5") (pin "2") (pinfunction "2_2") (pintype "passive"))
      (node (ref "U1") (pin "29") (pinfunction "DVDDK_29") (pintype "power_in"))
    )
    (net (code "114") (name "Net-(U1-RXDV)") (class "Default")
      (node (ref "R26") (pin "2") (pintype "passive"))
      (node (ref "U1") (pin "8") (pinfunction "RXDV_8") (pintype "output"))
    )
    (net (code "115") (name "VCC182") (class "Default")
      (node (ref "C20") (pin "2") (pinfunction "2_2") (pintype "passive"))
      (node (ref "C7") (pin "2") (pinfunction "2_2") (pintype "passive"))
      (node (ref "C8") (pin "2") (pinfunction "2_2") (pintype "passive"))
      (node (ref "C9") (pin "2") (pinfunction "2_2") (pintype "passive"))
      (node (ref "P4") (pin "12") (pinfunction "LED2+_12") (pintype "passive"))
      (node (ref "R12") (pin "1") (pintype "passive"))
      (node (ref "R13") (pin "1") (pintype "passive"))
      (node (ref "R26") (pin "1") (pintype "passive"))
      (node (ref "R29") (pin "2") (pintype "passive"))
      (node (ref "U1") (pin "14") (pinfunction "AVDD33_14") (pintype "power_in"))
      (node (ref "U1") (pin "30") (pinfunction "VDDIO_30") (pintype "power_in"))
      (node (ref "U1") (pin "7") (pinfunction "AVDD33_7") (pintype "power_in"))
    )
    (net (code "116") (name "unconnected-(P4-NC-Pad7)") (class "Default")
      (node (ref "P4") (pin "7") (pinfunction "NC_7") (pintype "passive"))
    )
    (net (code "117") (name "unconnected-(P5-RFU1-PadA8)") (class "Default")
      (node (ref "P5") (pin "A8") (pinfunction "RFU1_A8") (pintype "bidirectional+no_connect"))
    )
    (net (code "118") (name "unconnected-(P5-RFU1-PadB8)") (class "Default")
      (node (ref "P5") (pin "B8") (pinfunction "RFU1_B8") (pintype "bidirectional+no_connect"))
    )
    (net (code "119") (name "unconnected-(S2-NO-Pad3)") (class "Default")
      (node (ref "S2") (pin "3") (pinfunction "NO_3") (pintype "passive"))
    )
    (net (code "120") (name "unconnected-(U1-COL-Pad27)") (class "Default")
      (node (ref "U1") (pin "27") (pinfunction "COL_27") (pintype "output"))
    )
    (net (code "121") (name "unconnected-(U1-RXC-Pad13)") (class "Default")
      (node (ref "U1") (pin "13") (pinfunction "RXC_13") (pintype "output"))
    )
    (net (code "122") (name "unconnected-(U1-RXD[3]-Pad12)") (class "Default")
      (node (ref "U1") (pin "12") (pinfunction "RXD[3]_12") (pintype "output"))
    )
    (net (code "123") (name "unconnected-(U1-RXER-Pad28)") (class "Default")
      (node (ref "U1") (pin "28") (pinfunction "RXER_28") (pintype "output"))
    )
    (net (code "124") (name "unconnected-(U1-TXD[2]-Pad18)") (class "Default")
      (node (ref "U1") (pin "18") (pinfunction "TXD[2]_18") (pintype "input"))
    )
    (net (code "125") (name "unconnected-(U1-TXD[3]-Pad19)") (class "Default")
      (node (ref "U1") (pin "19") (pinfunction "TXD[3]_19") (pintype "input"))
    )
    (net (code "126") (name "unconnected-(U3-NC-Pad73)") (class "Default")
      (node (ref "U3") (pin "73") (pinfunction "NC_73") (pintype "tri_state"))
    )
    (net (code "127") (name "unconnected-(U3-PA0{slash}WKUP{slash}ADC0-Pad23)") (class "Default")
      (node (ref "U3") (pin "23") (pinfunction "PA0/WKUP/ADC0_23") (pintype "bidirectional"))
    )
    (net (code "128") (name "unconnected-(U3-PA3{slash}ADC3-Pad26)") (class "Default")
      (node (ref "U3") (pin "26") (pinfunction "PA3/ADC3_26") (pintype "bidirectional"))
    )
    (net (code "129") (name "unconnected-(U3-PB0{slash}ADC8-Pad35)") (class "Default")
      (node (ref "U3") (pin "35") (pinfunction "PB0/ADC8_35") (pintype "bidirectional"))
    )
    (net (code "130") (name "unconnected-(U3-PB1{slash}ADC9-Pad36)") (class "Default")
      (node (ref "U3") (pin "36") (pinfunction "PB1/ADC9_36") (pintype "bidirectional"))
    )
    (net (code "131") (name "unconnected-(U3-PB8-Pad95)") (class "Default")
      (node (ref "U3") (pin "95") (pinfunction "PB8_95") (pintype "bidirectional"))
    )
    (net (code "132") (name "unconnected-(U3-PB10-Pad47)") (class "Default")
      (node (ref "U3") (pin "47") (pinfunction "PB10_47") (pintype "bidirectional"))
    )
    (net (code "133") (name "unconnected-(U3-PC0{slash}ADC10-Pad15)") (class "Default")
      (node (ref "U3") (pin "15") (pinfunction "PC0/ADC10_15") (pintype "bidirectional"))
    )
    (net (code "134") (name "unconnected-(U3-PC2{slash}ADC12-Pad17)") (class "Default")
      (node (ref "U3") (pin "17") (pinfunction "PC2/ADC12_17") (pintype "bidirectional"))
    )
    (net (code "135") (name "unconnected-(U3-PC3{slash}ADC13-Pad18)") (class "Default")
      (node (ref "U3") (pin "18") (pinfunction "PC3/ADC13_18") (pintype "bidirectional"))
    )
  )
)
